# ESP32.net
KiCad netlist of a schematic drawn in Altium Designer
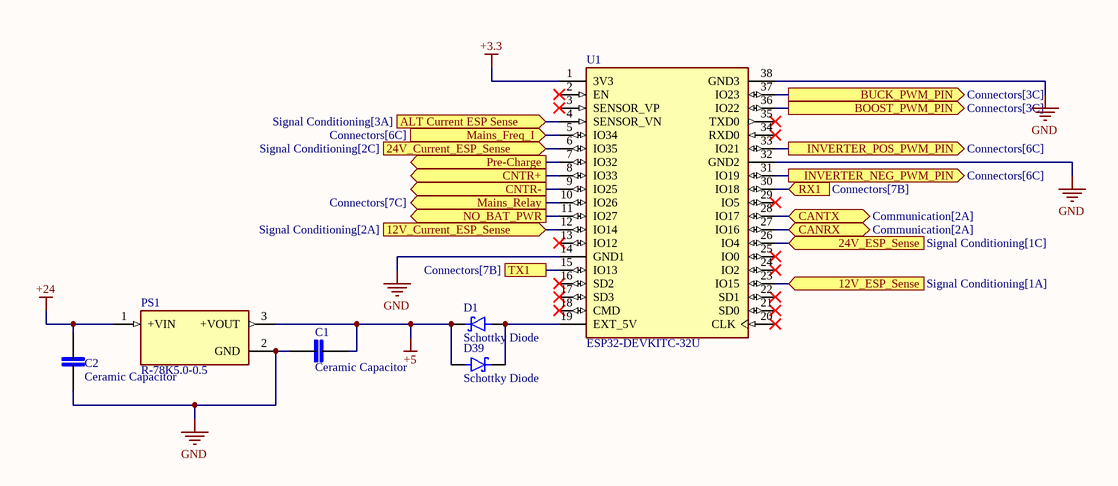
[diagram p0: ESP32.SchDoc]

(export (version "E")
  (design (tool "Eeschema 10.0.6"))
  (components
    (comp (ref "C1")
      (value "Ceramic Capacitor")
      (footprint "Ceramic Capacitor")
      (fields (field (name "MP") "LD051A121KAB2A") (field (name "MF") "AVX"))
      (libsource (lib "") (part "Ceramic Capacitor_1"))
    )
    (comp (ref "C2")
      (value "Ceramic Capacitor")
      (footprint "Ceramic Capacitor")
      (fields (field (name "MP") "LD051A121KAB2A") (field (name "MF") "AVX"))
      (libsource (lib "Capacitors Through Hole") (part "Ceramic Capacitor"))
    )
    (comp (ref "D1")
      (value "Schottky Diode")
      (footprint "Common Trhough Hole")
      (fields (field (name "MF") "Diodes Inc.") (field (name "MP") "1N5817-T"))
      (libsource (lib "Diodes Through Hole") (part "Schottky Diode"))
    )
    (comp (ref "D39")
      (value "Schottky Diode")
      (footprint "Common Trhough Hole")
      (fields (field (name "MF") "Diodes Inc.") (field (name "MP") "1N5817-T"))
      (libsource (lib "Diodes Through Hole") (part "Schottky Diode"))
    )
    (comp (ref "PS1")
      (value "R-78K5.0-0.5")
      (footprint "CONV_R-78K5.0-0.5")
      (description "0.5A DC/DC-Converter 'INNOLINE' SIP3 reg")
      (fields (field (name "MF") "Recom Power"))
      (libsource (lib "Voltage Regulators Through Hole") (part "R-78K5.0-0.5"))
    )
    (comp (ref "U1")
      (value "ESP32-DEVKITC-32U")
      (footprint "MODULE_ESP32-DEVKITC-32U")
      (fields (field (name "MF") "Espressif Systems"))
      (libsource (lib "MySCH_Library") (part "ESP32-DEVKITC-32U"))
    )
  )
  (nets
    (net (code "1") (name "+3.3") (class "Default")
      (node (ref "U1") (pin "1") (pinfunction "3V3_1") (pintype "power_in"))
    )
    (net (code "2") (name "+5") (class "Default")
      (node (ref "C1") (pin "2") (pinfunction "2_2") (pintype "passive"))
      (node (ref "D1") (pin "1") (pinfunction "K_1") (pintype "passive"))
      (node (ref "D39") (pin "2") (pinfunction "A_2") (pintype "passive"))
      (node (ref "PS1") (pin "3") (pinfunction "+VOUT_3") (pintype "output"))
    )
    (net (code "3") (name "+24") (class "Default")
      (node (ref "C2") (pin "2") (pinfunction "2_2") (pintype "passive"))
      (node (ref "PS1") (pin "1") (pinfunction "+VIN_1") (pintype "input"))
    )
    (net (code "4") (name "/12V_Current_ESP_Sense") (class "Default")
      (node (ref "U1") (pin "12") (pinfunction "IO14_12") (pintype "bidirectional"))
    )
    (net (code "5") (name "/12V_ESP_Sense") (class "Default")
      (node (ref "U1") (pin "23") (pinfunction "IO15_23") (pintype "bidirectional"))
    )
    (net (code "6") (name "/24V_Current_ESP_Sense") (class "Default")
      (node (ref "U1") (pin "6") (pinfunction "IO35_6") (pintype "bidirectional"))
    )
    (net (code "7") (name "/24V_ESP_Sense") (class "Default")
      (node (ref "U1") (pin "26") (pinfunction "IO4_26") (pintype "bidirectional"))
    )
    (net (code "8") (name "/ALT Current ESP Sense") (class "Default")
      (node (ref "U1") (pin "4") (pinfunction "SENSOR_VN_4") (pintype "input"))
    )
    (net (code "9") (name "/BOOST_PWM_PIN") (class "Default")
      (node (ref "U1") (pin "36") (pinfunction "IO22_36") (pintype "bidirectional"))
    )
    (net (code "10") (name "/BUCK_PWM_PIN") (class "Default")
      (node (ref "U1") (pin "37") (pinfunction "IO23_37") (pintype "bidirectional"))
    )
    (net (code "11") (name "/CANRX") (class "Default")
      (node (ref "U1") (pin "27") (pinfunction "IO16_27") (pintype "bidirectional"))
    )
    (net (code "12") (name "/CANTX") (class "Default")
      (node (ref "U1") (pin "28") (pinfunction "IO17_28") (pintype "bidirectional"))
    )
    (net (code "13") (name "/CNTR+") (class "Default")
      (node (ref "U1") (pin "8") (pinfunction "IO33_8") (pintype "bidirectional"))
    )
    (net (code "14") (name "/CNTR-") (class "Default")
      (node (ref "U1") (pin "9") (pinfunction "IO25_9") (pintype "bidirectional"))
    )
    (net (code "15") (name "/INVERTER_NEG_PWM_PIN") (class "Default")
      (node (ref "U1") (pin "31") (pinfunction "IO19_31") (pintype "bidirectional"))
    )
    (net (code "16") (name "/INVERTER_POS_PWM_PIN") (class "Default")
      (node (ref "U1") (pin "33") (pinfunction "IO21_33") (pintype "bidirectional"))
    )
    (net (code "17") (name "/Mains_Freq_I") (class "Default")
      (node (ref "U1") (pin "5") (pinfunction "IO34_5") (pintype "bidirectional"))
    )
    (net (code "18") (name "/Mains_Relay") (class "Default")
      (node (ref "U1") (pin "10") (pinfunction "IO26_10") (pintype "bidirectional"))
    )
    (net (code "19") (name "/NO_BAT_PWR") (class "Default")
      (node (ref "U1") (pin "11") (pinfunction "IO27_11") (pintype "bidirectional"))
    )
    (net (code "20") (name "/Pre-Charge") (class "Default")
      (node (ref "U1") (pin "7") (pinfunction "IO32_7") (pintype "bidirectional"))
    )
    (net (code "21") (name "/RX1") (class "Default")
      (node (ref "U1") (pin "30") (pinfunction "IO18_30") (pintype "bidirectional"))
    )
    (net (code "22") (name "/TX1") (class "Default")
      (node (ref "U1") (pin "15") (pinfunction "IO13_15") (pintype "bidirectional"))
    )
    (net (code "23") (name "GND") (class "Default")
      (node (ref "C1") (pin "1") (pinfunction "1_1") (pintype "passive"))
      (node (ref "C2") (pin "1") (pinfunction "1_1") (pintype "passive"))
      (node (ref "PS1") (pin "2") (pinfunction "GND_2") (pintype "power_in"))
      (node (ref "U1") (pin "14") (pinfunction "GND1_14") (pintype "power_in"))
      (node (ref "U1") (pin "32") (pinfunction "GND2_32") (pintype "power_in"))
      (node (ref "U1") (pin "38") (pinfunction "GND3_38") (pintype "power_in"))
    )
    (net (code "24") (name "Net-(D1-A)") (class "Default")
      (node (ref "D1") (pin "2") (pinfunction "A_2") (pintype "passive"))
      (node (ref "D39") (pin "1") (pinfunction "K_1") (pintype "passive"))
      (node (ref "U1") (pin "19") (pinfunction "EXT_5V_19") (pintype "power_in"))
    )
    (net (code "25") (name "unconnected-(U1-CLK-Pad20)") (class "Default")
      (node (ref "U1") (pin "20") (pinfunction "CLK_20") (pintype "input+no_connect"))
    )
    (net (code "26") (name "unconnected-(U1-CMD-Pad18)") (class "Default")
      (node (ref "U1") (pin "18") (pinfunction "CMD_18") (pintype "bidirectional+no_connect"))
    )
    (net (code "27") (name "unconnected-(U1-EN-Pad2)") (class "Default")
      (node (ref "U1") (pin "2") (pinfunction "EN_2") (pintype "input+no_connect"))
    )
    (net (code "28") (name "unconnected-(U1-IO0-Pad25)") (class "Default")
      (node (ref "U1") (pin "25") (pinfunction "IO0_25") (pintype "bidirectional+no_connect"))
    )
    (net (code "29") (name "unconnected-(U1-IO2-Pad24)") (class "Default")
      (node (ref "U1") (pin "24") (pinfunction "IO2_24") (pintype "bidirectional+no_connect"))
    )
    (net (code "30") (name "unconnected-(U1-IO5-Pad29)") (class "Default")
      (node (ref "U1") (pin "29") (pinfunction "IO5_29") (pintype "bidirectional+no_connect"))
    )
    (net (code "31") (name "unconnected-(U1-IO12-Pad13)") (class "Default")
      (node (ref "U1") (pin "13") (pinfunction "IO12_13") (pintype "bidirectional+no_connect"))
    )
    (net (code "32") (name "unconnected-(U1-RXD0-Pad34)") (class "Default")
      (node (ref "U1") (pin "34") (pinfunction "RXD0_34") (pintype "input+no_connect"))
    )
    (net (code "33") (name "unconnected-(U1-SD0-Pad21)") (class "Default")
      (node (ref "U1") (pin "21") (pinfunction "SD0_21") (pintype "bidirectional+no_connect"))
    )
    (net (code "34") (name "unconnected-(U1-SD1-Pad22)") (class "Default")
      (node (ref "U1") (pin "22") (pinfunction "SD1_22") (pintype "bidirectional+no_connect"))
    )
    (net (code "35") (name "unconnected-(U1-SD2-Pad16)") (class "Default")
      (node (ref "U1") (pin "16") (pinfunction "SD2_16") (pintype "bidirectional+no_connect"))
    )
    (net (code "36") (name "unconnected-(U1-SD3-Pad17)") (class "Default")
      (node (ref "U1") (pin "17") (pinfunction "SD3_17") (pintype "bidirectional+no_connect"))
    )
    (net (code "37") (name "unconnected-(U1-SENSOR_VP-Pad3)") (class "Default")
      (node (ref "U1") (pin "3") (pinfunction "SENSOR_VP_3") (pintype "input+no_connect"))
    )
    (net (code "38") (name "unconnected-(U1-TXD0-Pad35)") (class "Default")
      (node (ref "U1") (pin "35") (pinfunction "TXD0_35") (pintype "output+no_connect"))
    )
  )
)
